# light_sensor_basic.net
KiCad netlist of a schematic drawn in EAGLE
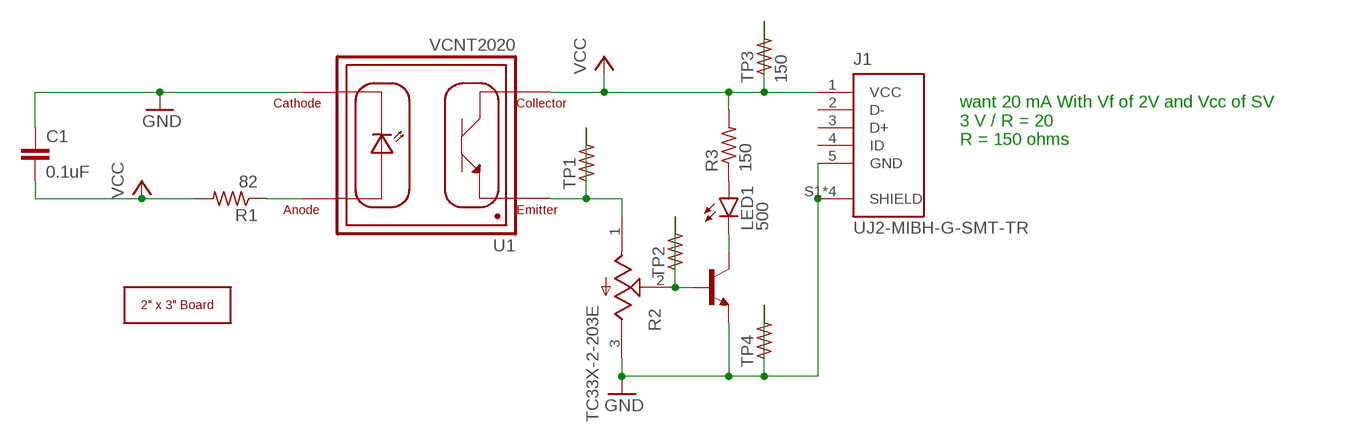
[diagram p0: schematic, sheet 1]

(export (version "E")
  (design (tool "Eeschema 10.0.6"))
  (components
    (comp (ref "C1")
      (value "0.1uF")
      (footprint "eagle-import:C1206")
      (libsource (lib "eagle-import") (part "C-EUC1206"))
    )
    (comp (ref "J1")
      (value "UJ2-MIBH-G-SMT-TR")
      (footprint "eagle-import:CUI_UJ2-MIBH-G-SMT-TR")
      (fields (field (name "MANUFACTURER") "CUI"))
      (libsource (lib "eagle-import") (part "UJ2-MIBH-G-SMT-TR"))
    )
    (comp (ref "LED1")
      (value "500")
      (footprint "eagle-import:SML0805")
      (libsource (lib "eagle-import") (part "LEDSML0805"))
    )
    (comp (ref "R1")
      (value "82")
      (footprint "eagle-import:R1206")
      (libsource (lib "eagle-import") (part "R-US_R1206"))
    )
    (comp (ref "R2")
      (value "TC33X-2-203E")
      (footprint "eagle-import:TRIM_TC33X-2-203E")
      (fields (field (name "DIGIKEY_PART_NUMBER") "TC33X-2-203ETR-ND") (field (name "MF") "Bourns"))
      (libsource (lib "eagle-import") (part "TC33X-2-203E"))
    )
    (comp (ref "R3")
      (value "150")
      (footprint "eagle-import:R0805")
      (libsource (lib "eagle-import") (part "R-US_R0805"))
    )
    (comp (ref "T1")
      (value "-NPN-SOT23-EBC")
      (footprint "eagle-import:SOT23-EBC")
      (libsource (lib "eagle-import") (part "-NPN-SOT23-EBC"))
    )
    (comp (ref "TP1")
      (value "R-US_R1206")
      (footprint "eagle-import:R1206")
      (libsource (lib "eagle-import") (part "R-US_R1206"))
    )
    (comp (ref "TP2")
      (value "R-US_R1206")
      (footprint "eagle-import:R1206")
      (libsource (lib "eagle-import") (part "R-US_R1206"))
    )
    (comp (ref "TP3")
      (value "150")
      (footprint "eagle-import:R0805")
      (libsource (lib "eagle-import") (part "R-US_R0805"))
    )
    (comp (ref "TP4")
      (value "R-US_R1206")
      (footprint "eagle-import:R1206")
      (libsource (lib "eagle-import") (part "R-US_R1206"))
    )
    (comp (ref "U$1")
      (value "2X3_BOARD_V2")
      (footprint "eagle-import:2X3_BOARD_V2")
      (libsource (lib "eagle-import") (part "2X3_BOARD_V2"))
    )
    (comp (ref "U1")
      (value "VCNT2020")
      (footprint "eagle-import:XDCR_VCNT2020")
      (fields (field (name "DIGIKEY_PART_NUMBER") "VCNT2020TR-ND") (field (name "MF") "Vishay"))
      (libsource (lib "eagle-import") (part "VCNT2020"))
    )
  )
  (nets
    (net (code "1") (name "GND") (class "Default")
      (node (ref "C1") (pin "1") (pinfunction "1_1") (pintype "passive"))
      (node (ref "J1") (pin "5") (pinfunction "GND_5") (pintype "power_in"))
      (node (ref "J1") (pin "S1") (pinfunction "SHIELD_S1") (pintype "passive"))
      (node (ref "J1") (pin "S2") (pinfunction "SHIELD_S2") (pintype "passive"))
      (node (ref "J1") (pin "S3") (pinfunction "SHIELD_S3") (pintype "passive"))
      (node (ref "J1") (pin "S4") (pinfunction "SHIELD_S4") (pintype "passive"))
      (node (ref "R2") (pin "3") (pinfunction "CW_3") (pintype "passive"))
      (node (ref "T1") (pin "E") (pinfunction "E_E") (pintype "passive"))
      (node (ref "TP4") (pin "1") (pinfunction "1_1") (pintype "passive"))
      (node (ref "TP4") (pin "2") (pinfunction "2_2") (pintype "passive"))
      (node (ref "U1") (pin "4") (pinfunction "CATHODE_4") (pintype "passive"))
    )
    (net (code "2") (name "Net-(LED1-PadA)") (class "Default")
      (node (ref "LED1") (pin "A") (pinfunction "A_A") (pintype "passive"))
      (node (ref "R3") (pin "1") (pinfunction "1_1") (pintype "passive"))
    )
    (net (code "3") (name "Net-(LED1-PadC)") (class "Default")
      (node (ref "LED1") (pin "C") (pinfunction "C_C") (pintype "passive"))
      (node (ref "T1") (pin "C") (pinfunction "C_C") (pintype "passive"))
    )
    (net (code "4") (name "Net-(R2-CCW)") (class "Default")
      (node (ref "R2") (pin "1") (pinfunction "CCW_1") (pintype "passive"))
      (node (ref "TP1") (pin "1") (pinfunction "1_1") (pintype "passive"))
      (node (ref "TP1") (pin "2") (pinfunction "2_2") (pintype "passive"))
      (node (ref "U1") (pin "1") (pinfunction "EMITTER_1") (pintype "passive"))
    )
    (net (code "5") (name "Net-(R2-W)") (class "Default")
      (node (ref "R2") (pin "2") (pinfunction "W_2") (pintype "passive"))
      (node (ref "T1") (pin "B") (pinfunction "B_B") (pintype "passive"))
      (node (ref "TP2") (pin "1") (pinfunction "1_1") (pintype "passive"))
      (node (ref "TP2") (pin "2") (pinfunction "2_2") (pintype "passive"))
    )
    (net (code "6") (name "Net-(U1-ANODE)") (class "Default")
      (node (ref "R1") (pin "1") (pinfunction "1_1") (pintype "passive"))
      (node (ref "U1") (pin "3") (pinfunction "ANODE_3") (pintype "passive"))
    )
    (net (code "7") (name "VCC") (class "Default")
      (node (ref "C1") (pin "2") (pinfunction "2_2") (pintype "passive"))
      (node (ref "J1") (pin "1") (pinfunction "VCC_1") (pintype "power_in"))
      (node (ref "R1") (pin "2") (pinfunction "2_2") (pintype "passive"))
      (node (ref "R3") (pin "2") (pinfunction "2_2") (pintype "passive"))
      (node (ref "TP3") (pin "1") (pinfunction "1_1") (pintype "passive"))
      (node (ref "TP3") (pin "2") (pinfunction "2_2") (pintype "passive"))
      (node (ref "U1") (pin "2") (pinfunction "COLLECTOR_2") (pintype "passive"))
    )
    (net (code "8") (name "unconnected-(J1-D+-Pad3)") (class "Default")
      (node (ref "J1") (pin "3") (pinfunction "D+_3") (pintype "bidirectional"))
    )
    (net (code "9") (name "unconnected-(J1-D--Pad2)") (class "Default")
      (node (ref "J1") (pin "2") (pinfunction "D-_2") (pintype "bidirectional"))
    )
    (net (code "10") (name "unconnected-(J1-ID-Pad4)") (class "Default")
      (node (ref "J1") (pin "4") (pinfunction "ID_4") (pintype "bidirectional"))
    )
  )
)
